# 464421_22-01_Power.net
KiCad netlist of a schematic drawn in Altium Designer
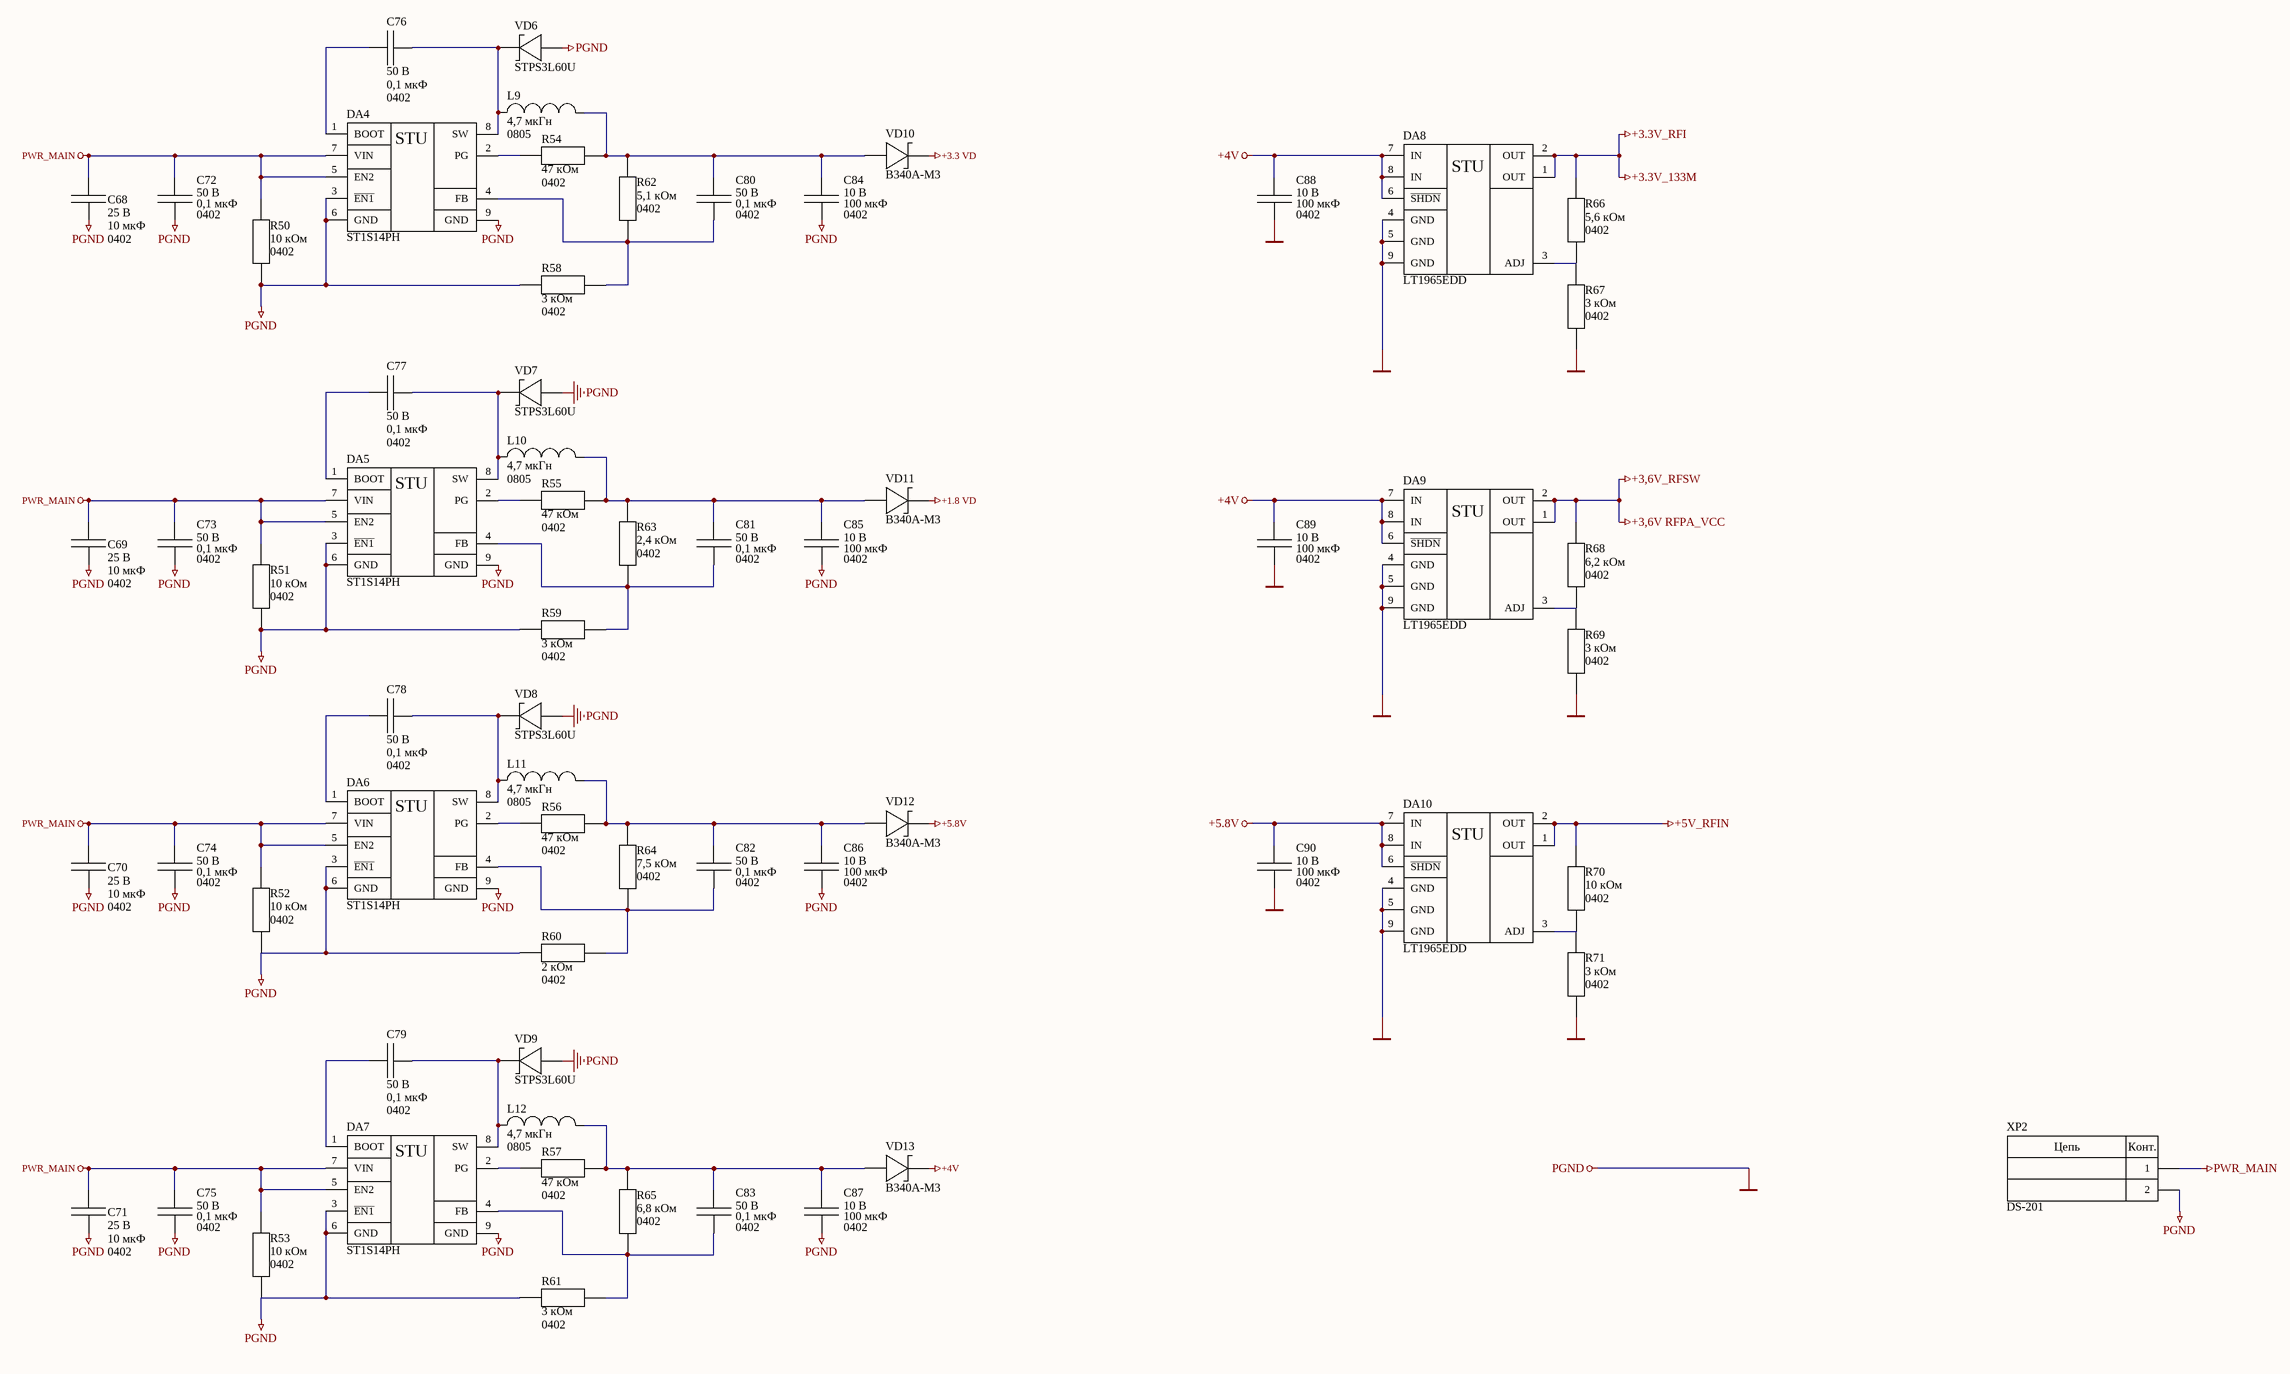
[diagram p0: МПСУ.464421.22-01 Power.SchDoc]

(export (version "E")
  (design (tool "Eeschema 10.0.6"))
  (components
    (comp (ref "C68")
      (value "10 мкФ")
      (footprint "Passive_V2_0:CAPC100X50X55L20N")
      (description "Capacitor 0402")
      (fields
        (field (name "PARTNUMBER") "GRM188R61E106KA73J")
        (field (name "MANUFACTURER") "Murata")
        (field (name "PEAK_CONDITION") "25 В")
        (field (name "PACKAGE") "0402")
        (field (name "DESIGNER") "Свидерский")
      )
      (libsource (lib "Passive_V2_0") (part "C 0402"))
    )
    (comp (ref "C69")
      (value "10 мкФ")
      (footprint "Passive_V2_0:CAPC100X50X55L20N")
      (description "Capacitor 0402")
      (fields
        (field (name "PARTNUMBER") "GRM188R61E106KA73J")
        (field (name "MANUFACTURER") "Murata")
        (field (name "PEAK_CONDITION") "25 В")
        (field (name "PACKAGE") "0402")
        (field (name "DESIGNER") "Свидерский")
      )
      (libsource (lib "Passive_V2_0") (part "C 0402"))
    )
    (comp (ref "C70")
      (value "10 мкФ")
      (footprint "Passive_V2_0:CAPC100X50X55L20N")
      (description "Capacitor 0402")
      (fields
        (field (name "PARTNUMBER") "GRM188R61E106KA73J")
        (field (name "MANUFACTURER") "Murata")
        (field (name "PEAK_CONDITION") "25 В")
        (field (name "PACKAGE") "0402")
        (field (name "DESIGNER") "Свидерский")
      )
      (libsource (lib "Passive_V2_0") (part "C 0402"))
    )
    (comp (ref "C71")
      (value "10 мкФ")
      (footprint "Passive_V2_0:CAPC100X50X55L20N")
      (description "Capacitor 0402")
      (fields
        (field (name "PARTNUMBER") "GRM188R61E106KA73J")
        (field (name "MANUFACTURER") "Murata")
        (field (name "PEAK_CONDITION") "25 В")
        (field (name "PACKAGE") "0402")
        (field (name "DESIGNER") "Свидерский")
      )
      (libsource (lib "Passive_V2_0") (part "C 0402"))
    )
    (comp (ref "C72")
      (value "0,1 мкФ")
      (footprint "Passive_V2_0:CAPC100X50X55L20N")
      (description "Capacitor 0402")
      (fields
        (field (name "PARTNUMBER") "GRM155R71H104KE14J")
        (field (name "MANUFACTURER") "Murata")
        (field (name "PEAK_CONDITION") "50 В")
        (field (name "PACKAGE") "0402")
        (field (name "DESIGNER") "Свидерский")
      )
      (libsource (lib "Passive_V2_0") (part "C 0402"))
    )
    (comp (ref "C73")
      (value "0,1 мкФ")
      (footprint "Passive_V2_0:CAPC100X50X55L20N")
      (description "Capacitor 0402")
      (fields
        (field (name "PARTNUMBER") "GRM155R71H104KE14J")
        (field (name "MANUFACTURER") "Murata")
        (field (name "PEAK_CONDITION") "50 В")
        (field (name "PACKAGE") "0402")
        (field (name "DESIGNER") "Свидерский")
      )
      (libsource (lib "Passive_V2_0") (part "C 0402"))
    )
    (comp (ref "C74")
      (value "0,1 мкФ")
      (footprint "Passive_V2_0:CAPC100X50X55L20N")
      (description "Capacitor 0402")
      (fields
        (field (name "PARTNUMBER") "GRM155R71H104KE14J")
        (field (name "MANUFACTURER") "Murata")
        (field (name "PEAK_CONDITION") "50 В")
        (field (name "PACKAGE") "0402")
        (field (name "DESIGNER") "Свидерский")
      )
      (libsource (lib "Passive_V2_0") (part "C 0402"))
    )
    (comp (ref "C75")
      (value "0,1 мкФ")
      (footprint "Passive_V2_0:CAPC100X50X55L20N")
      (description "Capacitor 0402")
      (fields
        (field (name "PARTNUMBER") "GRM155R71H104KE14J")
        (field (name "MANUFACTURER") "Murata")
        (field (name "PEAK_CONDITION") "50 В")
        (field (name "PACKAGE") "0402")
        (field (name "DESIGNER") "Свидерский")
      )
      (libsource (lib "Passive_V2_0") (part "C 0402"))
    )
    (comp (ref "C76")
      (value "0,1 мкФ")
      (footprint "Passive_V2_0:CAPC100X50X55L20N")
      (description "Capacitor 0402")
      (fields
        (field (name "PARTNUMBER") "GRM155R71H104KE14J")
        (field (name "MANUFACTURER") "Murata")
        (field (name "PEAK_CONDITION") "50 В")
        (field (name "PACKAGE") "0402")
        (field (name "DESIGNER") "Свидерский")
      )
      (libsource (lib "Passive_V2_0") (part "C 0402"))
    )
    (comp (ref "C77")
      (value "0,1 мкФ")
      (footprint "Passive_V2_0:CAPC100X50X55L20N")
      (description "Capacitor 0402")
      (fields
        (field (name "PARTNUMBER") "GRM155R71H104KE14J")
        (field (name "MANUFACTURER") "Murata")
        (field (name "PEAK_CONDITION") "50 В")
        (field (name "PACKAGE") "0402")
        (field (name "DESIGNER") "Свидерский")
      )
      (libsource (lib "Passive_V2_0") (part "C 0402"))
    )
    (comp (ref "C78")
      (value "0,1 мкФ")
      (footprint "Passive_V2_0:CAPC100X50X55L20N")
      (description "Capacitor 0402")
      (fields
        (field (name "PARTNUMBER") "GRM155R71H104KE14J")
        (field (name "MANUFACTURER") "Murata")
        (field (name "PEAK_CONDITION") "50 В")
        (field (name "PACKAGE") "0402")
        (field (name "DESIGNER") "Свидерский")
      )
      (libsource (lib "Passive_V2_0") (part "C 0402"))
    )
    (comp (ref "C79")
      (value "0,1 мкФ")
      (footprint "Passive_V2_0:CAPC100X50X55L20N")
      (description "Capacitor 0402")
      (fields
        (field (name "PARTNUMBER") "GRM155R71H104KE14J")
        (field (name "MANUFACTURER") "Murata")
        (field (name "PEAK_CONDITION") "50 В")
        (field (name "PACKAGE") "0402")
        (field (name "DESIGNER") "Свидерский")
      )
      (libsource (lib "Passive_V2_0") (part "C 0402"))
    )
    (comp (ref "C80")
      (value "0,1 мкФ")
      (footprint "Passive_V2_0:CAPC100X50X55L20N")
      (description "Capacitor 0402")
      (fields
        (field (name "PARTNUMBER") "GRM155R71H104KE14J")
        (field (name "MANUFACTURER") "Murata")
        (field (name "PEAK_CONDITION") "50 В")
        (field (name "PACKAGE") "0402")
        (field (name "DESIGNER") "Свидерский")
      )
      (libsource (lib "Passive_V2_0") (part "C 0402"))
    )
    (comp (ref "C81")
      (value "0,1 мкФ")
      (footprint "Passive_V2_0:CAPC100X50X55L20N")
      (description "Capacitor 0402")
      (fields
        (field (name "PARTNUMBER") "GRM155R71H104KE14J")
        (field (name "MANUFACTURER") "Murata")
        (field (name "PEAK_CONDITION") "50 В")
        (field (name "PACKAGE") "0402")
        (field (name "DESIGNER") "Свидерский")
      )
      (libsource (lib "Passive_V2_0") (part "C 0402"))
    )
    (comp (ref "C82")
      (value "0,1 мкФ")
      (footprint "Passive_V2_0:CAPC100X50X55L20N")
      (description "Capacitor 0402")
      (fields
        (field (name "PARTNUMBER") "GRM155R71H104KE14J")
        (field (name "MANUFACTURER") "Murata")
        (field (name "PEAK_CONDITION") "50 В")
        (field (name "PACKAGE") "0402")
        (field (name "DESIGNER") "Свидерский")
      )
      (libsource (lib "Passive_V2_0") (part "C 0402"))
    )
    (comp (ref "C83")
      (value "0,1 мкФ")
      (footprint "Passive_V2_0:CAPC100X50X55L20N")
      (description "Capacitor 0402")
      (fields
        (field (name "PARTNUMBER") "GRM155R71H104KE14J")
        (field (name "MANUFACTURER") "Murata")
        (field (name "PEAK_CONDITION") "50 В")
        (field (name "PACKAGE") "0402")
        (field (name "DESIGNER") "Свидерский")
      )
      (libsource (lib "Passive_V2_0") (part "C 0402"))
    )
    (comp (ref "C84")
      (value "100 мкФ")
      (footprint "Passive_V2_0:CAPC100X50X55L20N")
      (description "Capacitor 0402")
      (fields
        (field (name "PARTNUMBER") "C3216JB1A107M160AC")
        (field (name "MANUFACTURER") "TDK")
        (field (name "PEAK_CONDITION") "10 В")
        (field (name "PACKAGE") "0402")
        (field (name "DESIGNER") "Свидерский")
      )
      (libsource (lib "Passive_V2_0") (part "C 0402"))
    )
    (comp (ref "C85")
      (value "100 мкФ")
      (footprint "Passive_V2_0:CAPC100X50X55L20N")
      (description "Capacitor 0402")
      (fields
        (field (name "PARTNUMBER") "C3216JB1A107M160AC")
        (field (name "MANUFACTURER") "TDK")
        (field (name "PEAK_CONDITION") "10 В")
        (field (name "PACKAGE") "0402")
        (field (name "DESIGNER") "Свидерский")
      )
      (libsource (lib "Passive_V2_0") (part "C 0402"))
    )
    (comp (ref "C86")
      (value "100 мкФ")
      (footprint "Passive_V2_0:CAPC100X50X55L20N")
      (description "Capacitor 0402")
      (fields
        (field (name "PARTNUMBER") "C3216JB1A107M160AC")
        (field (name "MANUFACTURER") "TDK")
        (field (name "PEAK_CONDITION") "10 В")
        (field (name "PACKAGE") "0402")
        (field (name "DESIGNER") "Свидерский")
      )
      (libsource (lib "Passive_V2_0") (part "C 0402"))
    )
    (comp (ref "C87")
      (value "100 мкФ")
      (footprint "Passive_V2_0:CAPC100X50X55L20N")
      (description "Capacitor 0402")
      (fields
        (field (name "PARTNUMBER") "C3216JB1A107M160AC")
        (field (name "MANUFACTURER") "TDK")
        (field (name "PEAK_CONDITION") "10 В")
        (field (name "PACKAGE") "0402")
        (field (name "DESIGNER") "Свидерский")
      )
      (libsource (lib "Passive_V2_0") (part "C 0402"))
    )
    (comp (ref "C88")
      (value "100 мкФ")
      (footprint "Passive_V2_0:CAPC100X50X55L20N")
      (description "Capacitor 0402")
      (fields
        (field (name "PARTNUMBER") "C3216JB1A107M160AC")
        (field (name "MANUFACTURER") "TDK")
        (field (name "PEAK_CONDITION") "10 В")
        (field (name "PACKAGE") "0402")
        (field (name "DESIGNER") "Свидерский")
      )
      (libsource (lib "Passive_V2_0") (part "C 0402"))
    )
    (comp (ref "C89")
      (value "100 мкФ")
      (footprint "Passive_V2_0:CAPC100X50X55L20N")
      (description "Capacitor 0402")
      (fields
        (field (name "PARTNUMBER") "C3216JB1A107M160AC")
        (field (name "MANUFACTURER") "TDK")
        (field (name "PEAK_CONDITION") "10 В")
        (field (name "PACKAGE") "0402")
        (field (name "DESIGNER") "Свидерский")
      )
      (libsource (lib "Passive_V2_0") (part "C 0402"))
    )
    (comp (ref "C90")
      (value "100 мкФ")
      (footprint "Passive_V2_0:CAPC100X50X55L20N")
      (description "Capacitor 0402")
      (fields
        (field (name "PARTNUMBER") "C3216JB1A107M160AC")
        (field (name "MANUFACTURER") "TDK")
        (field (name "PEAK_CONDITION") "10 В")
        (field (name "PACKAGE") "0402")
        (field (name "DESIGNER") "Свидерский")
      )
      (libsource (lib "Passive_V2_0") (part "C 0402"))
    )
    (comp (ref "DA4")
      (value "ST1S14PH")
      (footprint "IC_V2_0:SOP127P600X175_HS-9N")
      (description "Up to 3 A step-down switching regulator")
      (fields
        (field (name "MANUFACTURER") "STMicroelectronics")
        (field (name "PARTNUMBER") "ST1S14PH")
        (field (name "DESIGNER") "Затонская")
      )
      (libsource (lib "IC_V2_0") (part "ST1S14PH"))
    )
    (comp (ref "DA5")
      (value "ST1S14PH")
      (footprint "IC_V2_0:SOP127P600X175_HS-9N")
      (description "Up to 3 A step-down switching regulator")
      (fields
        (field (name "MANUFACTURER") "STMicroelectronics")
        (field (name "PARTNUMBER") "ST1S14PH")
        (field (name "DESIGNER") "Затонская")
      )
      (libsource (lib "IC_V2_0") (part "ST1S14PH"))
    )
    (comp (ref "DA6")
      (value "ST1S14PH")
      (footprint "IC_V2_0:SOP127P600X175_HS-9N")
      (description "Up to 3 A step-down switching regulator")
      (fields
        (field (name "MANUFACTURER") "STMicroelectronics")
        (field (name "PARTNUMBER") "ST1S14PH")
        (field (name "DESIGNER") "Затонская")
      )
      (libsource (lib "IC_V2_0") (part "ST1S14PH"))
    )
    (comp (ref "DA7")
      (value "ST1S14PH")
      (footprint "IC_V2_0:SOP127P600X175_HS-9N")
      (description "Up to 3 A step-down switching regulator")
      (fields
        (field (name "MANUFACTURER") "STMicroelectronics")
        (field (name "PARTNUMBER") "ST1S14PH")
        (field (name "DESIGNER") "Затонская")
      )
      (libsource (lib "IC_V2_0") (part "ST1S14PH"))
    )
    (comp (ref "DA8")
      (value "LT1965EDD")
      (footprint "IC_V2_0:SON9P50_300X300X80L40X25T244X160N")
      (description "1.1A, Low Noise,  Low Dropout Linear Regulator")
      (fields
        (field (name "MANUFACTURER") "Analog Devices")
        (field (name "PARTNUMBER") "LT1965EDD")
        (field (name "DESIGNER") "Свидерский")
      )
      (libsource (lib "IC_V2_0") (part "LT1965*DD"))
    )
    (comp (ref "DA9")
      (value "LT1965EDD")
      (footprint "IC_V2_0:SON9P50_300X300X80L40X25T244X160N")
      (description "1.1A, Low Noise,  Low Dropout Linear Regulator")
      (fields
        (field (name "MANUFACTURER") "Analog Devices")
        (field (name "PARTNUMBER") "LT1965EDD")
        (field (name "DESIGNER") "Свидерский")
      )
      (libsource (lib "IC_V2_0") (part "LT1965*DD"))
    )
    (comp (ref "DA10")
      (value "LT1965EDD")
      (footprint "IC_V2_0:SON9P50_300X300X80L40X25T244X160N")
      (description "1.1A, Low Noise,  Low Dropout Linear Regulator")
      (fields
        (field (name "MANUFACTURER") "Analog Devices")
        (field (name "PARTNUMBER") "LT1965EDD")
        (field (name "DESIGNER") "Свидерский")
      )
      (libsource (lib "IC_V2_0") (part "LT1965*DD"))
    )
    (comp (ref "L9")
      (value "4,7 мкГн")
      (footprint "Passive_V2_0:INDC200X120X110L50N")
      (description "Inductor 0805")
      (fields
        (field (name "PARTNUMBER") "LQM21PZ4R7NGRD")
        (field (name "TOLERANCE") "30 %")
        (field (name "PACKAGE") "0805")
        (field (name "DESIGNER") "Свидерский")
      )
      (libsource (lib "Passive_V2_0") (part "L 0805"))
    )
    (comp (ref "L10")
      (value "4,7 мкГн")
      (footprint "Passive_V2_0:INDC200X120X110L50N")
      (description "Inductor 0805")
      (fields
        (field (name "PARTNUMBER") "LQM21PZ4R7NGRD")
        (field (name "TOLERANCE") "30 %")
        (field (name "PACKAGE") "0805")
        (field (name "DESIGNER") "Свидерский")
      )
      (libsource (lib "Passive_V2_0") (part "L 0805"))
    )
    (comp (ref "L11")
      (value "4,7 мкГн")
      (footprint "Passive_V2_0:INDC200X120X110L50N")
      (description "Inductor 0805")
      (fields
        (field (name "PARTNUMBER") "LQM21PZ4R7NGRD")
        (field (name "TOLERANCE") "30 %")
        (field (name "PACKAGE") "0805")
        (field (name "DESIGNER") "Свидерский")
      )
      (libsource (lib "Passive_V2_0") (part "L 0805"))
    )
    (comp (ref "L12")
      (value "4,7 мкГн")
      (footprint "Passive_V2_0:INDC200X120X110L50N")
      (description "Inductor 0805")
      (fields
        (field (name "PARTNUMBER") "LQM21PZ4R7NGRD")
        (field (name "TOLERANCE") "30 %")
        (field (name "PACKAGE") "0805")
        (field (name "DESIGNER") "Свидерский")
      )
      (libsource (lib "Passive_V2_0") (part "L 0805"))
    )
    (comp (ref "R50")
      (value "10 кОм")
      (footprint "Passive_V2_0:RESC100X50X40L25N")
      (description "Resistor 0402")
      (fields
        (field (name "PARTNUMBER") "RI0402L103JT")
        (field (name "TOLERANCE") "5 %")
        (field (name "PACKAGE") "0402")
        (field (name "DESIGNER") "Свидерский")
      )
      (libsource (lib "") (part "R 0402_1"))
    )
    (comp (ref "R51")
      (value "10 кОм")
      (footprint "Passive_V2_0:RESC100X50X40L25N")
      (description "Resistor 0402")
      (fields
        (field (name "PARTNUMBER") "RI0402L103JT")
        (field (name "TOLERANCE") "5 %")
        (field (name "PACKAGE") "0402")
        (field (name "DESIGNER") "Свидерский")
      )
      (libsource (lib "") (part "R 0402_1"))
    )
    (comp (ref "R52")
      (value "10 кОм")
      (footprint "Passive_V2_0:RESC100X50X40L25N")
      (description "Resistor 0402")
      (fields
        (field (name "PARTNUMBER") "RI0402L103JT")
        (field (name "TOLERANCE") "5 %")
        (field (name "PACKAGE") "0402")
        (field (name "DESIGNER") "Свидерский")
      )
      (libsource (lib "") (part "R 0402_1"))
    )
    (comp (ref "R53")
      (value "10 кОм")
      (footprint "Passive_V2_0:RESC100X50X40L25N")
      (description "Resistor 0402")
      (fields
        (field (name "PARTNUMBER") "RI0402L103JT")
        (field (name "TOLERANCE") "5 %")
        (field (name "PACKAGE") "0402")
        (field (name "DESIGNER") "Свидерский")
      )
      (libsource (lib "") (part "R 0402_1"))
    )
    (comp (ref "R54")
      (value "47 кОм")
      (footprint "Passive_V2_0:RESC100X50X40L25N")
      (description "Resistor 0402")
      (fields
        (field (name "PARTNUMBER") "RI0402L473JT")
        (field (name "TOLERANCE") "5 %")
        (field (name "PACKAGE") "0402")
        (field (name "DESIGNER") "Свидерский")
      )
      (libsource (lib "") (part "R 0402_2"))
    )
    (comp (ref "R55")
      (value "47 кОм")
      (footprint "Passive_V2_0:RESC100X50X40L25N")
      (description "Resistor 0402")
      (fields
        (field (name "PARTNUMBER") "RI0402L473JT")
        (field (name "TOLERANCE") "5 %")
        (field (name "PACKAGE") "0402")
        (field (name "DESIGNER") "Свидерский")
      )
      (libsource (lib "") (part "R 0402_2"))
    )
    (comp (ref "R56")
      (value "47 кОм")
      (footprint "Passive_V2_0:RESC100X50X40L25N")
      (description "Resistor 0402")
      (fields
        (field (name "PARTNUMBER") "RI0402L473JT")
        (field (name "TOLERANCE") "5 %")
        (field (name "PACKAGE") "0402")
        (field (name "DESIGNER") "Свидерский")
      )
      (libsource (lib "") (part "R 0402_2"))
    )
    (comp (ref "R57")
      (value "47 кОм")
      (footprint "Passive_V2_0:RESC100X50X40L25N")
      (description "Resistor 0402")
      (fields
        (field (name "PARTNUMBER") "RI0402L473JT")
        (field (name "TOLERANCE") "5 %")
        (field (name "PACKAGE") "0402")
        (field (name "DESIGNER") "Свидерский")
      )
      (libsource (lib "") (part "R 0402_2"))
    )
    (comp (ref "R58")
      (value "3 кОм")
      (footprint "Passive_V2_0:RESC100X50X40L25N")
      (description "Resistor 0402")
      (fields
        (field (name "PARTNUMBER") "RC0402FR-073KL")
        (field (name "TOLERANCE") "1 %")
        (field (name "PACKAGE") "0402")
        (field (name "DESIGNER") "Свидерский")
      )
      (libsource (lib "Passive_V2_0") (part "R 0402"))
    )
    (comp (ref "R59")
      (value "3 кОм")
      (footprint "Passive_V2_0:RESC100X50X40L25N")
      (description "Resistor 0402")
      (fields
        (field (name "PARTNUMBER") "RC0402FR-073KL")
        (field (name "TOLERANCE") "1 %")
        (field (name "PACKAGE") "0402")
        (field (name "DESIGNER") "Свидерский")
      )
      (libsource (lib "Passive_V2_0") (part "R 0402"))
    )
    (comp (ref "R60")
      (value "2 кОм")
      (footprint "Passive_V2_0:RESC100X50X40L25N")
      (description "Resistor 0402")
      (fields
        (field (name "PARTNUMBER") "RC-02W202JT")
        (field (name "TOLERANCE") "5 %")
        (field (name "PACKAGE") "0402")
        (field (name "DESIGNER") "Свидерский")
      )
      (libsource (lib "Passive_V2_0") (part "R 0402"))
    )
    (comp (ref "R61")
      (value "3 кОм")
      (footprint "Passive_V2_0:RESC100X50X40L25N")
      (description "Resistor 0402")
      (fields
        (field (name "PARTNUMBER") "RC0402FR-073KL")
        (field (name "TOLERANCE") "1 %")
        (field (name "PACKAGE") "0402")
        (field (name "DESIGNER") "Свидерский")
      )
      (libsource (lib "Passive_V2_0") (part "R 0402"))
    )
    (comp (ref "R62")
      (value "5,1 кОм")
      (footprint "Passive_V2_0:RESC100X50X40L25N")
      (description "Resistor 0402")
      (fields
        (field (name "PARTNUMBER") "RI0402L5101FT")
        (field (name "TOLERANCE") "1 %")
        (field (name "PACKAGE") "0402")
        (field (name "DESIGNER") "Свидерский")
      )
      (libsource (lib "") (part "R 0402_1"))
    )
    (comp (ref "R63")
      (value "2,4 кОм")
      (footprint "Passive_V2_0:RESC100X50X40L25N")
      (description "Resistor 0402")
      (fields
        (field (name "PARTNUMBER") "RC0402FR-072K4L")
        (field (name "TOLERANCE") "1 %")
        (field (name "PACKAGE") "0402")
        (field (name "DESIGNER") "Свидерский")
      )
      (libsource (lib "") (part "R 0402_1"))
    )
    (comp (ref "R64")
      (value "7,5 кОм")
      (footprint "Passive_V2_0:RESC100X50X40L25N")
      (description "Resistor 0402")
      (fields
        (field (name "PARTNUMBER") "RI0402L7501FT")
        (field (name "TOLERANCE") "1 %")
        (field (name "PACKAGE") "0402")
        (field (name "DESIGNER") "Свидерский")
      )
      (libsource (lib "") (part "R 0402_1"))
    )
    (comp (ref "R65")
      (value "6,8 кОм")
      (footprint "Passive_V2_0:RESC100X50X40L25N")
      (description "Resistor 0402")
      (fields
        (field (name "PARTNUMBER") "RC-02W682JT")
        (field (name "TOLERANCE") "5 %")
        (field (name "PACKAGE") "0402")
        (field (name "DESIGNER") "Свидерский")
      )
      (libsource (lib "") (part "R 0402_1"))
    )
    (comp (ref "R66")
      (value "5,6 кОм")
      (footprint "Passive_V2_0:RESC100X50X40L25N")
      (description "Resistor 0402")
      (fields
        (field (name "PARTNUMBER") "RI0402L5601FT")
        (field (name "TOLERANCE") "1 %")
        (field (name "PACKAGE") "0402")
        (field (name "DESIGNER") "Свидерский")
      )
      (libsource (lib "") (part "R 0402_1"))
    )
    (comp (ref "R67")
      (value "3 кОм")
      (footprint "Passive_V2_0:RESC100X50X40L25N")
      (description "Resistor 0402")
      (fields
        (field (name "PARTNUMBER") "RC0402FR-073KL")
        (field (name "TOLERANCE") "1 %")
        (field (name "PACKAGE") "0402")
        (field (name "DESIGNER") "Свидерский")
      )
      (libsource (lib "") (part "R 0402_1"))
    )
    (comp (ref "R68")
      (value "6,2 кОм")
      (footprint "Passive_V2_0:RESC100X50X40L25N")
      (description "Resistor 0402")
      (fields
        (field (name "PARTNUMBER") "RI0402L622JT")
        (field (name "TOLERANCE") "5 %")
        (field (name "PACKAGE") "0402")
        (field (name "DESIGNER") "Свидерский")
      )
      (libsource (lib "") (part "R 0402_1"))
    )
    (comp (ref "R69")
      (value "3 кОм")
      (footprint "Passive_V2_0:RESC100X50X40L25N")
      (description "Resistor 0402")
      (fields
        (field (name "PARTNUMBER") "RC0402FR-073KL")
        (field (name "TOLERANCE") "1 %")
        (field (name "PACKAGE") "0402")
        (field (name "DESIGNER") "Свидерский")
      )
      (libsource (lib "") (part "R 0402_1"))
    )
    (comp (ref "R70")
      (value "10 кОм")
      (footprint "Passive_V2_0:RESC100X50X40L25N")
      (description "Resistor 0402")
      (fields
        (field (name "PARTNUMBER") "RI0402L103JT")
        (field (name "TOLERANCE") "5 %")
        (field (name "PACKAGE") "0402")
        (field (name "DESIGNER") "Свидерский")
      )
      (libsource (lib "") (part "R 0402_1"))
    )
    (comp (ref "R71")
      (value "3 кОм")
      (footprint "Passive_V2_0:RESC100X50X40L25N")
      (description "Resistor 0402")
      (fields
        (field (name "PARTNUMBER") "RC0402FR-073KL")
        (field (name "TOLERANCE") "1 %")
        (field (name "PACKAGE") "0402")
        (field (name "DESIGNER") "Свидерский")
      )
      (libsource (lib "") (part "R 0402_1"))
    )
    (comp (ref "VD6")
      (value "STPS3L60U")
      (footprint "Discrete_V2_0:DIOM5436X11N")
      (description "60 V, 3 A low drop Schottky rectifier")
      (fields
        (field (name "MANUFACTURER") "Diodes Incorporated")
        (field (name "PARTNUMBER") "STPS3L60U")
        (field (name "DESIGNER") "Затонская")
      )
      (libsource (lib "Discrete_V2_0") (part "STPS3L60"))
    )
    (comp (ref "VD7")
      (value "STPS3L60U")
      (footprint "Discrete_V2_0:DIOM5436X11N")
      (description "60 V, 3 A low drop Schottky rectifier")
      (fields
        (field (name "MANUFACTURER") "Diodes Incorporated")
        (field (name "PARTNUMBER") "STPS3L60U")
        (field (name "DESIGNER") "Затонская")
      )
      (libsource (lib "Discrete_V2_0") (part "STPS3L60"))
    )
    (comp (ref "VD8")
      (value "STPS3L60U")
      (footprint "Discrete_V2_0:DIOM5436X11N")
      (description "60 V, 3 A low drop Schottky rectifier")
      (fields
        (field (name "MANUFACTURER") "Diodes Incorporated")
        (field (name "PARTNUMBER") "STPS3L60U")
        (field (name "DESIGNER") "Затонская")
      )
      (libsource (lib "Discrete_V2_0") (part "STPS3L60"))
    )
    (comp (ref "VD9")
      (value "STPS3L60U")
      (footprint "Discrete_V2_0:DIOM5436X11N")
      (description "60 V, 3 A low drop Schottky rectifier")
      (fields
        (field (name "MANUFACTURER") "Diodes Incorporated")
        (field (name "PARTNUMBER") "STPS3L60U")
        (field (name "DESIGNER") "Затонская")
      )
      (libsource (lib "Discrete_V2_0") (part "STPS3L60"))
    )
    (comp (ref "VD10")
      (value "B340A-M3")
      (footprint "Discrete_V2_0:DIOC4227X10N")
      (description "SURFACE MOUNT SCHOTTKY BARRIER RECTIFIER")
      (fields
        (field (name "MANUFACTURER") "Diodes Incorporated")
        (field (name "PARTNUMBER") "B340A-M3")
        (field (name "DESIGNER") "Затонская")
      )
      (libsource (lib "Discrete_V2_0") (part "B340A-M3"))
    )
    (comp (ref "VD11")
      (value "B340A-M3")
      (footprint "Discrete_V2_0:DIOC4227X10N")
      (description "SURFACE MOUNT SCHOTTKY BARRIER RECTIFIER")
      (fields
        (field (name "MANUFACTURER") "Diodes Incorporated")
        (field (name "PARTNUMBER") "B340A-M3")
        (field (name "DESIGNER") "Затонская")
      )
      (libsource (lib "Discrete_V2_0") (part "B340A-M3"))
    )
    (comp (ref "VD12")
      (value "B340A-M3")
      (footprint "Discrete_V2_0:DIOC4227X10N")
      (description "SURFACE MOUNT SCHOTTKY BARRIER RECTIFIER")
      (fields
        (field (name "MANUFACTURER") "Diodes Incorporated")
        (field (name "PARTNUMBER") "B340A-M3")
        (field (name "DESIGNER") "Затонская")
      )
      (libsource (lib "Discrete_V2_0") (part "B340A-M3"))
    )
    (comp (ref "VD13")
      (value "B340A-M3")
      (footprint "Discrete_V2_0:DIOC4227X10N")
      (description "SURFACE MOUNT SCHOTTKY BARRIER RECTIFIER")
      (fields
        (field (name "MANUFACTURER") "Diodes Incorporated")
        (field (name "PARTNUMBER") "B340A-M3")
        (field (name "DESIGNER") "Затонская")
      )
      (libsource (lib "Discrete_V2_0") (part "B340A-M3"))
    )
    (comp (ref "XP2")
      (value "DS-201")
      (footprint "Connectors_V2_0:DS-201")
      (description "DC supply 2 PIN DC-005 2.1x5.5mm")
      (fields
        (field (name "MANUFACTURER") "AMASS")
        (field (name "PARTNUMBER") "DS-201")
        (field (name "DESIGNER") "Лазба")
      )
      (libsource (lib "Connectors_V2_0") (part "DS-201"))
    )
  )
  (nets
    (net (code "1") (name "+1.8 VD") (class "Default")
      (node (ref "VD11") (pin "1") (pinfunction "C_1") (pintype "passive"))
    )
    (net (code "2") (name "+3,6V RFPA_VCC") (class "Default")
      (node (ref "DA9") (pin "1") (pinfunction "OUT_1") (pintype "passive"))
      (node (ref "DA9") (pin "2") (pinfunction "OUT_2") (pintype "passive"))
      (node (ref "R68") (pin "1") (pinfunction "1_1") (pintype "passive"))
    )
    (net (code "3") (name "+3.3 VD") (class "Default")
      (node (ref "VD10") (pin "1") (pinfunction "C_1") (pintype "passive"))
    )
    (net (code "4") (name "+3.3V_133M") (class "Default")
      (node (ref "DA8") (pin "1") (pinfunction "OUT_1") (pintype "passive"))
      (node (ref "DA8") (pin "2") (pinfunction "OUT_2") (pintype "passive"))
      (node (ref "R66") (pin "1") (pinfunction "1_1") (pintype "passive"))
    )
    (net (code "5") (name "+4V") (class "Default")
      (node (ref "C88") (pin "1") (pinfunction "1_1") (pintype "passive"))
      (node (ref "C89") (pin "1") (pinfunction "1_1") (pintype "passive"))
      (node (ref "DA8") (pin "6") (pinfunction "~{SHDN}_6") (pintype "passive"))
      (node (ref "DA8") (pin "7") (pinfunction "IN_7") (pintype "passive"))
      (node (ref "DA8") (pin "8") (pinfunction "IN_8") (pintype "passive"))
      (node (ref "DA9") (pin "6") (pinfunction "~{SHDN}_6") (pintype "passive"))
      (node (ref "DA9") (pin "7") (pinfunction "IN_7") (pintype "passive"))
      (node (ref "DA9") (pin "8") (pinfunction "IN_8") (pintype "passive"))
      (node (ref "VD13") (pin "1") (pinfunction "C_1") (pintype "passive"))
    )
    (net (code "6") (name "+5.8V") (class "Default")
      (node (ref "C90") (pin "1") (pinfunction "1_1") (pintype "passive"))
      (node (ref "DA10") (pin "6") (pinfunction "~{SHDN}_6") (pintype "passive"))
      (node (ref "DA10") (pin "7") (pinfunction "IN_7") (pintype "passive"))
      (node (ref "DA10") (pin "8") (pinfunction "IN_8") (pintype "passive"))
      (node (ref "VD12") (pin "1") (pinfunction "C_1") (pintype "passive"))
    )
    (net (code "7") (name "+5V_RFIN") (class "Default")
      (node (ref "DA10") (pin "1") (pinfunction "OUT_1") (pintype "passive"))
      (node (ref "DA10") (pin "2") (pinfunction "OUT_2") (pintype "passive"))
      (node (ref "R70") (pin "1") (pinfunction "1_1") (pintype "passive"))
    )
    (net (code "9") (name "GND") (class "Default")
      (node (ref "C68") (pin "2") (pinfunction "2_2") (pintype "passive"))
      (node (ref "C69") (pin "2") (pinfunction "2_2") (pintype "passive"))
      (node (ref "C70") (pin "2") (pinfunction "2_2") (pintype "passive"))
      (node (ref "C71") (pin "2") (pinfunction "2_2") (pintype "passive"))
      (node (ref "C72") (pin "2") (pinfunction "2_2") (pintype "passive"))
      (node (ref "C73") (pin "2") (pinfunction "2_2") (pintype "passive"))
      (node (ref "C74") (pin "2") (pinfunction "2_2") (pintype "passive"))
      (node (ref "C75") (pin "2") (pinfunction "2_2") (pintype "passive"))
      (node (ref "C84") (pin "2") (pinfunction "2_2") (pintype "passive"))
      (node (ref "C85") (pin "2") (pinfunction "2_2") (pintype "passive"))
      (node (ref "C86") (pin "2") (pinfunction "2_2") (pintype "passive"))
      (node (ref "C87") (pin "2") (pinfunction "2_2") (pintype "passive"))
      (node (ref "C88") (pin "2") (pinfunction "2_2") (pintype "passive"))
      (node (ref "C89") (pin "2") (pinfunction "2_2") (pintype "passive"))
      (node (ref "C90") (pin "2") (pinfunction "2_2") (pintype "passive"))
      (node (ref "DA10") (pin "4") (pinfunction "GND_4") (pintype "passive"))
      (node (ref "DA10") (pin "5") (pinfunction "GND_5") (pintype "passive"))
      (node (ref "DA10") (pin "9") (pinfunction "GND_9") (pintype "passive"))
      (node (ref "DA4") (pin "3") (pinfunction "~{EN1}_3") (pintype "passive"))
      (node (ref "DA4") (pin "6") (pinfunction "GND_6") (pintype "passive"))
      (node (ref "DA4") (pin "9") (pinfunction "GND_9") (pintype "passive"))
      (node (ref "DA5") (pin "3") (pinfunction "~{EN1}_3") (pintype "passive"))
      (node (ref "DA5") (pin "6") (pinfunction "GND_6") (pintype "passive"))
      (node (ref "DA5") (pin "9") (pinfunction "GND_9") (pintype "passive"))
      (node (ref "DA6") (pin "3") (pinfunction "~{EN1}_3") (pintype "passive"))
      (node (ref "DA6") (pin "6") (pinfunction "GND_6") (pintype "passive"))
      (node (ref "DA6") (pin "9") (pinfunction "GND_9") (pintype "passive"))
      (node (ref "DA7") (pin "3") (pinfunction "~{EN1}_3") (pintype "passive"))
      (node (ref "DA7") (pin "6") (pinfunction "GND_6") (pintype "passive"))
      (node (ref "DA7") (pin "9") (pinfunction "GND_9") (pintype "passive"))
      (node (ref "DA8") (pin "4") (pinfunction "GND_4") (pintype "passive"))
      (node (ref "DA8") (pin "5") (pinfunction "GND_5") (pintype "passive"))
      (node (ref "DA8") (pin "9") (pinfunction "GND_9") (pintype "passive"))
      (node (ref "DA9") (pin "4") (pinfunction "GND_4") (pintype "passive"))
      (node (ref "DA9") (pin "5") (pinfunction "GND_5") (pintype "passive"))
      (node (ref "DA9") (pin "9") (pinfunction "GND_9") (pintype "passive"))
      (node (ref "R50") (pin "2") (pinfunction "2_2") (pintype "passive"))
      (node (ref "R51") (pin "2") (pinfunction "2_2") (pintype "passive"))
      (node (ref "R52") (pin "2") (pinfunction "2_2") (pintype "passive"))
      (node (ref "R53") (pin "2") (pinfunction "2_2") (pintype "passive"))
      (node (ref "R58") (pin "2") (pinfunction "2_2") (pintype "passive"))
      (node (ref "R59") (pin "2") (pinfunction "2_2") (pintype "passive"))
      (node (ref "R60") (pin "2") (pinfunction "2_2") (pintype "passive"))
      (node (ref "R61") (pin "2") (pinfunction "2_2") (pintype "passive"))
      (node (ref "R67") (pin "2") (pinfunction "2_2") (pintype "passive"))
      (node (ref "R69") (pin "2") (pinfunction "2_2") (pintype "passive"))
      (node (ref "R71") (pin "2") (pinfunction "2_2") (pintype "passive"))
      (node (ref "VD6") (pin "2") (pinfunction "A_2") (pintype "passive"))
      (node (ref "VD7") (pin "2") (pinfunction "A_2") (pintype "passive"))
      (node (ref "VD8") (pin "2") (pinfunction "A_2") (pintype "passive"))
      (node (ref "VD9") (pin "2") (pinfunction "A_2") (pintype "passive"))
      (node (ref "XP2") (pin "2") (pinfunction "2_2") (pintype "passive"))
    )
    (net (code "10") (name "Net-(DA4-BOOT)") (class "Default")
      (node (ref "C76") (pin "1") (pinfunction "1_1") (pintype "passive"))
      (node (ref "DA4") (pin "1") (pinfunction "BOOT_1") (pintype "passive"))
    )
    (net (code "11") (name "Net-(DA4-FB)") (class "Default")
      (node (ref "C80") (pin "2") (pinfunction "2_2") (pintype "passive"))
      (node (ref "DA4") (pin "4") (pinfunction "FB_4") (pintype "passive"))
      (node (ref "R58") (pin "1") (pinfunction "1_1") (pintype "passive"))
      (node (ref "R62") (pin "2") (pinfunction "2_2") (pintype "passive"))
    )
    (net (code "12") (name "Net-(DA4-PG)") (class "Default")
      (node (ref "DA4") (pin "2") (pinfunction "PG_2") (pintype "passive"))
      (node (ref "R54") (pin "1") (pinfunction "1_1") (pintype "passive"))
    )
    (net (code "13") (name "Net-(DA4-SW)") (class "Default")
      (node (ref "C76") (pin "2") (pinfunction "2_2") (pintype "passive"))
      (node (ref "DA4") (pin "8") (pinfunction "SW_8") (pintype "passive"))
      (node (ref "L9") (pin "1") (pinfunction "1_1") (pintype "passive"))
      (node (ref "VD6") (pin "1") (pinfunction "C_1") (pintype "passive"))
    )
    (net (code "14") (name "Net-(DA5-BOOT)") (class "Default")
      (node (ref "C77") (pin "1") (pinfunction "1_1") (pintype "passive"))
      (node (ref "DA5") (pin "1") (pinfunction "BOOT_1") (pintype "passive"))
    )
    (net (code "15") (name "Net-(DA5-FB)") (class "Default")
      (node (ref "C81") (pin "2") (pinfunction "2_2") (pintype "passive"))
      (node (ref "DA5") (pin "4") (pinfunction "FB_4") (pintype "passive"))
      (node (ref "R59") (pin "1") (pinfunction "1_1") (pintype "passive"))
      (node (ref "R63") (pin "2") (pinfunction "2_2") (pintype "passive"))
    )
    (net (code "16") (name "Net-(DA5-PG)") (class "Default")
      (node (ref "DA5") (pin "2") (pinfunction "PG_2") (pintype "passive"))
      (node (ref "R55") (pin "1") (pinfunction "1_1") (pintype "passive"))
    )
    (net (code "17") (name "Net-(DA5-SW)") (class "Default")
      (node (ref "C77") (pin "2") (pinfunction "2_2") (pintype "passive"))
      (node (ref "DA5") (pin "8") (pinfunction "SW_8") (pintype "passive"))
      (node (ref "L10") (pin "1") (pinfunction "1_1") (pintype "passive"))
      (node (ref "VD7") (pin "1") (pinfunction "C_1") (pintype "passive"))
    )
    (net (code "18") (name "Net-(DA6-BOOT)") (class "Default")
      (node (ref "C78") (pin "1") (pinfunction "1_1") (pintype "passive"))
      (node (ref "DA6") (pin "1") (pinfunction "BOOT_1") (pintype "passive"))
    )
    (net (code "19") (name "Net-(DA6-FB)") (class "Default")
      (node (ref "C82") (pin "2") (pinfunction "2_2") (pintype "passive"))
      (node (ref "DA6") (pin "4") (pinfunction "FB_4") (pintype "passive"))
      (node (ref "R60") (pin "1") (pinfunction "1_1") (pintype "passive"))
      (node (ref "R64") (pin "2") (pinfunction "2_2") (pintype "passive"))
    )
    (net (code "20") (name "Net-(DA6-PG)") (class "Default")
      (node (ref "DA6") (pin "2") (pinfunction "PG_2") (pintype "passive"))
      (node (ref "R56") (pin "1") (pinfunction "1_1") (pintype "passive"))
    )
    (net (code "21") (name "Net-(DA6-SW)") (class "Default")
      (node (ref "C78") (pin "2") (pinfunction "2_2") (pintype "passive"))
      (node (ref "DA6") (pin "8") (pinfunction "SW_8") (pintype "passive"))
      (node (ref "L11") (pin "1") (pinfunction "1_1") (pintype "passive"))
      (node (ref "VD8") (pin "1") (pinfunction "C_1") (pintype "passive"))
    )
    (net (code "22") (name "Net-(DA7-BOOT)") (class "Default")
      (node (ref "C79") (pin "1") (pinfunction "1_1") (pintype "passive"))
      (node (ref "DA7") (pin "1") (pinfunction "BOOT_1") (pintype "passive"))
    )
    (net (code "23") (name "Net-(DA7-FB)") (class "Default")
      (node (ref "C83") (pin "2") (pinfunction "2_2") (pintype "passive"))
      (node (ref "DA7") (pin "4") (pinfunction "FB_4") (pintype "passive"))
      (node (ref "R61") (pin "1") (pinfunction "1_1") (pintype "passive"))
      (node (ref "R65") (pin "2") (pinfunction "2_2") (pintype "passive"))
    )
    (net (code "24") (name "Net-(DA7-PG)") (class "Default")
      (node (ref "DA7") (pin "2") (pinfunction "PG_2") (pintype "passive"))
      (node (ref "R57") (pin "1") (pinfunction "1_1") (pintype "passive"))
    )
    (net (code "25") (name "Net-(DA7-SW)") (class "Default")
      (node (ref "C79") (pin "2") (pinfunction "2_2") (pintype "passive"))
      (node (ref "DA7") (pin "8") (pinfunction "SW_8") (pintype "passive"))
      (node (ref "L12") (pin "1") (pinfunction "1_1") (pintype "passive"))
      (node (ref "VD9") (pin "1") (pinfunction "C_1") (pintype "passive"))
    )
    (net (code "26") (name "Net-(DA8-ADJ)") (class "Default")
      (node (ref "DA8") (pin "3") (pinfunction "ADJ_3") (pintype "passive"))
      (node (ref "R66") (pin "2") (pinfunction "2_2") (pintype "passive"))
      (node (ref "R67") (pin "1") (pinfunction "1_1") (pintype "passive"))
    )
    (net (code "27") (name "Net-(DA9-ADJ)") (class "Default")
      (node (ref "DA9") (pin "3") (pinfunction "ADJ_3") (pintype "passive"))
      (node (ref "R68") (pin "2") (pinfunction "2_2") (pintype "passive"))
      (node (ref "R69") (pin "1") (pinfunction "1_1") (pintype "passive"))
    )
    (net (code "28") (name "Net-(DA10-ADJ)") (class "Default")
      (node (ref "DA10") (pin "3") (pinfunction "ADJ_3") (pintype "passive"))
      (node (ref "R70") (pin "2") (pinfunction "2_2") (pintype "passive"))
      (node (ref "R71") (pin "1") (pinfunction "1_1") (pintype "passive"))
    )
    (net (code "29") (name "Net-(VD10-A)") (class "Default")
      (node (ref "C80") (pin "1") (pinfunction "1_1") (pintype "passive"))
      (node (ref "C84") (pin "1") (pinfunction "1_1") (pintype "passive"))
      (node (ref "L9") (pin "2") (pinfunction "2_2") (pintype "passive"))
      (node (ref "R54") (pin "2") (pinfunction "2_2") (pintype "passive"))
      (node (ref "R62") (pin "1") (pinfunction "1_1") (pintype "passive"))
      (node (ref "VD10") (pin "2") (pinfunction "A_2") (pintype "passive"))
    )
    (net (code "30") (name "Net-(VD11-A)") (class "Default")
      (node (ref "C81") (pin "1") (pinfunction "1_1") (pintype "passive"))
      (node (ref "C85") (pin "1") (pinfunction "1_1") (pintype "passive"))
      (node (ref "L10") (pin "2") (pinfunction "2_2") (pintype "passive"))
      (node (ref "R55") (pin "2") (pinfunction "2_2") (pintype "passive"))
      (node (ref "R63") (pin "1") (pinfunction "1_1") (pintype "passive"))
      (node (ref "VD11") (pin "2") (pinfunction "A_2") (pintype "passive"))
    )
    (net (code "31") (name "Net-(VD12-A)") (class "Default")
      (node (ref "C82") (pin "1") (pinfunction "1_1") (pintype "passive"))
      (node (ref "C86") (pin "1") (pinfunction "1_1") (pintype "passive"))
      (node (ref "L11") (pin "2") (pinfunction "2_2") (pintype "passive"))
      (node (ref "R56") (pin "2") (pinfunction "2_2") (pintype "passive"))
      (node (ref "R64") (pin "1") (pinfunction "1_1") (pintype "passive"))
      (node (ref "VD12") (pin "2") (pinfunction "A_2") (pintype "passive"))
    )
    (net (code "32") (name "Net-(VD13-A)") (class "Default")
      (node (ref "C83") (pin "1") (pinfunction "1_1") (pintype "passive"))
      (node (ref "C87") (pin "1") (pinfunction "1_1") (pintype "passive"))
      (node (ref "L12") (pin "2") (pinfunction "2_2") (pintype "passive"))
      (node (ref "R57") (pin "2") (pinfunction "2_2") (pintype "passive"))
      (node (ref "R65") (pin "1") (pinfunction "1_1") (pintype "passive"))
      (node (ref "VD13") (pin "2") (pinfunction "A_2") (pintype "passive"))
    )
    (net (code "33") (name "PWR_MAIN") (class "Default")
      (node (ref "C68") (pin "1") (pinfunction "1_1") (pintype "passive"))
      (node (ref "C69") (pin "1") (pinfunction "1_1") (pintype "passive"))
      (node (ref "C70") (pin "1") (pinfunction "1_1") (pintype "passive"))
      (node (ref "C71") (pin "1") (pinfunction "1_1") (pintype "passive"))
      (node (ref "C72") (pin "1") (pinfunction "1_1") (pintype "passive"))
      (node (ref "C73") (pin "1") (pinfunction "1_1") (pintype "passive"))
      (node (ref "C74") (pin "1") (pinfunction "1_1") (pintype "passive"))
      (node (ref "C75") (pin "1") (pinfunction "1_1") (pintype "passive"))
      (node (ref "DA4") (pin "5") (pinfunction "EN2_5") (pintype "passive"))
      (node (ref "DA4") (pin "7") (pinfunction "VIN_7") (pintype "passive"))
      (node (ref "DA5") (pin "5") (pinfunction "EN2_5") (pintype "passive"))
      (node (ref "DA5") (pin "7") (pinfunction "VIN_7") (pintype "passive"))
      (node (ref "DA6") (pin "5") (pinfunction "EN2_5") (pintype "passive"))
      (node (ref "DA6") (pin "7") (pinfunction "VIN_7") (pintype "passive"))
      (node (ref "DA7") (pin "5") (pinfunction "EN2_5") (pintype "passive"))
      (node (ref "DA7") (pin "7") (pinfunction "VIN_7") (pintype "passive"))
      (node (ref "R50") (pin "1") (pinfunction "1_1") (pintype "passive"))
      (node (ref "R51") (pin "1") (pinfunction "1_1") (pintype "passive"))
      (node (ref "R52") (pin "1") (pinfunction "1_1") (pintype "passive"))
      (node (ref "R53") (pin "1") (pinfunction "1_1") (pintype "passive"))
      (node (ref "XP2") (pin "1") (pinfunction "1_1") (pintype "passive"))
    )
  )
)
